# power_supply.net
KiCad netlist of a schematic drawn in Altium Designer
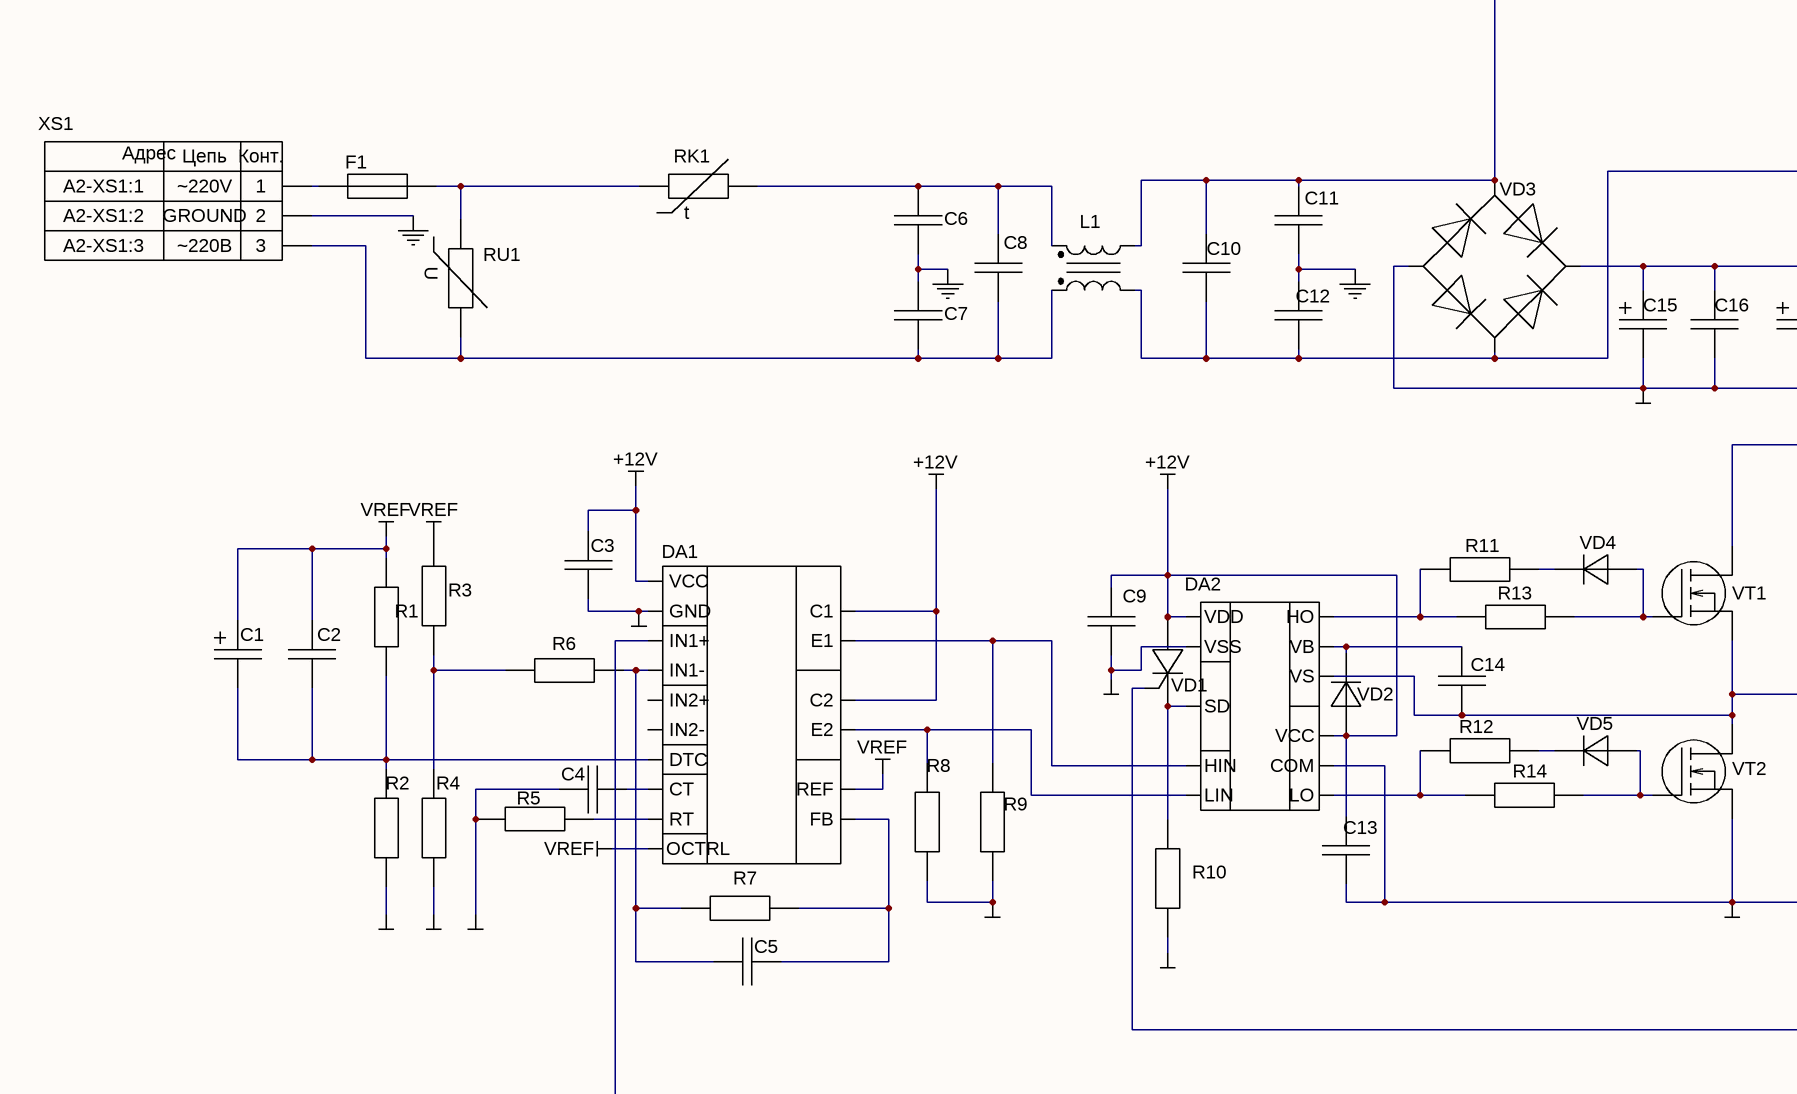
[diagram p0: power_supply.SchDoc, left]
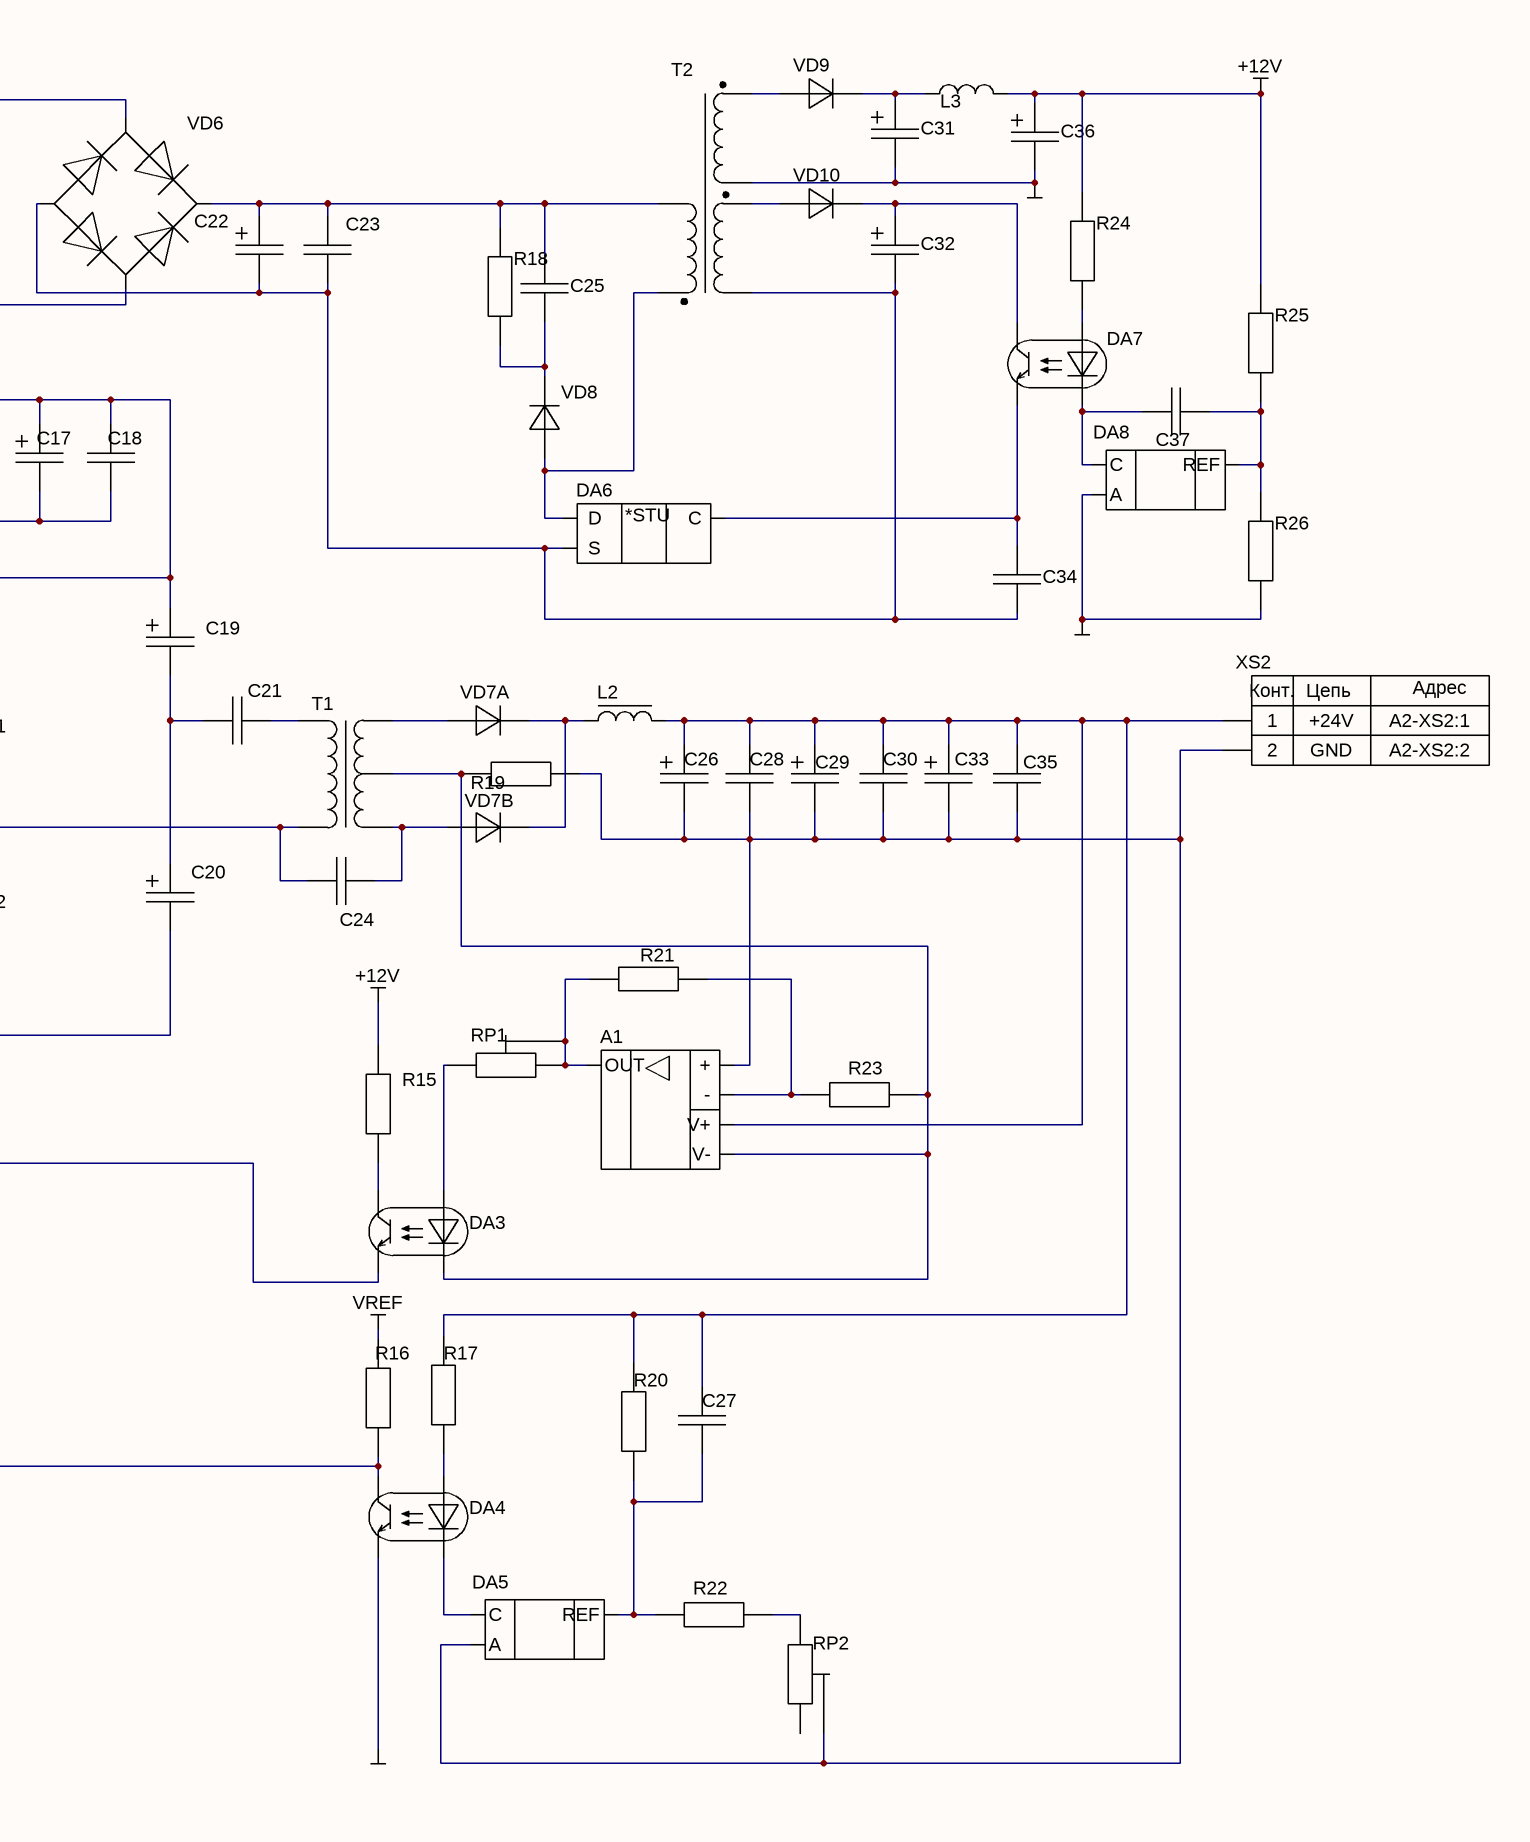
[diagram p1: power_supply.SchDoc, right]

(export (version "E")
  (design (tool "Eeschema 10.0.6"))
  (components
    (comp (ref "A1") (value "LMV321ILT") (libsource (lib "elems") (part "single_channel_op_amp")))
    (comp (ref "C1") (value "100мкФ") (libsource (lib "elems") (part "C_pol")))
    (comp (ref "C2") (value "100 нФ") (libsource (lib "elems") (part "C_const")))
    (comp (ref "C3") (value "1 мкФ") (libsource (lib "") (part "C_const_1")))
    (comp (ref "C4") (value "2.2 нФ") (libsource (lib "elems") (part "C_const")))
    (comp (ref "C5") (value "1 мкФ") (libsource (lib "elems") (part "C_const")))
    (comp (ref "C6") (value "1 нФ") (footprint "CAP: B32021") (libsource (lib "elems") (part "C_const")))
    (comp (ref "C7") (value "1 нФ") (footprint "CAP: B32021") (libsource (lib "elems") (part "C_const")))
    (comp (ref "C8") (value "470 нФ") (footprint "B32922") (libsource (lib "elems") (part "C_const")))
    (comp (ref "C9") (value "1 мкФ") (libsource (lib "elems") (part "C_const")))
    (comp (ref "C10") (value "470 нФ") (footprint "B32922") (libsource (lib "elems") (part "C_const")))
    (comp (ref "C11") (value "1 нФ") (footprint "CAP: B32021") (libsource (lib "elems") (part "C_const")))
    (comp (ref "C12") (value "1 нФ") (footprint "CAP: B32021") (libsource (lib "elems") (part "C_const")))
    (comp (ref "C13") (value "1 мкФ") (libsource (lib "elems") (part "C_const")))
    (comp (ref "C14") (value "1 мкФ") (libsource (lib "elems") (part "C_const")))
    (comp (ref "C15") (value "220 мкФ") (libsource (lib "elems") (part "C_pol")))
    (comp (ref "C16") (value "100 нФ") (libsource (lib "elems") (part "C_const")))
    (comp (ref "C17") (value "220 мкФ") (libsource (lib "elems") (part "C_pol")))
    (comp (ref "C18") (value "100 нФ") (libsource (lib "elems") (part "C_const")))
    (comp (ref "C19") (value "10 мкФ") (libsource (lib "elems") (part "C_pol")))
    (comp (ref "C20") (value "10 мкФ") (libsource (lib "elems") (part "C_pol")))
    (comp (ref "C21") (value "1 мкФ") (libsource (lib "") (part "C_const_2")))
    (comp (ref "C22") (value "100 мкФ") (libsource (lib "elems") (part "C_pol")))
    (comp (ref "C23") (value "100 нФ") (libsource (lib "elems") (part "C_const")))
    (comp (ref "C24") (value "1 нФ") (libsource (lib "elems") (part "C_const")))
    (comp (ref "C25") (value "C_const") (libsource (lib "elems") (part "C_const")))
    (comp (ref "C26") (value "3300 мкФ") (libsource (lib "elems") (part "C_pol")))
    (comp (ref "C27") (value "1 мкФ") (libsource (lib "elems") (part "C_const")))
    (comp (ref "C28") (value "100 нФ") (libsource (lib "elems") (part "C_const")))
    (comp (ref "C29") (value "3300 мкФ") (libsource (lib "elems") (part "C_pol")))
    (comp (ref "C30") (value "100 нФ") (libsource (lib "elems") (part "C_const")))
    (comp (ref "C31") (value "C_pol") (libsource (lib "elems") (part "C_pol")))
    (comp (ref "C32") (value "C_pol") (libsource (lib "elems") (part "C_pol")))
    (comp (ref "C33") (value "3300 мкФ") (libsource (lib "elems") (part "C_pol")))
    (comp (ref "C34") (value "C_const") (libsource (lib "elems") (part "C_const")))
    (comp (ref "C35") (value "100 нФ") (libsource (lib "elems") (part "C_const")))
    (comp (ref "C36") (value "C_pol") (libsource (lib "elems") (part "C_pol")))
    (comp (ref "C37") (value "C_const") (libsource (lib "elems") (part "C_const")))
    (comp (ref "DA1") (value "tl494") (libsource (lib "elems") (part "tl494")))
    (comp (ref "DA2") (value "ir2110") (libsource (lib "elems") (part "ir2110")))
    (comp (ref "DA3") (value "LTV-814") (libsource (lib "elems") (part "opt")))
    (comp (ref "DA4") (value "LTV-814") (libsource (lib "elems") (part "opt")))
    (comp (ref "DA5") (value "tl431") (libsource (lib "elems") (part "tl431")))
    (comp (ref "DA6") (value "top227") (libsource (lib "elems") (part "top227")))
    (comp (ref "DA7") (value "opt") (libsource (lib "elems") (part "opt")))
    (comp (ref "DA8") (value "tl431") (libsource (lib "elems") (part "tl431")))
    (comp (ref "F1") (value "2А") (footprint "FUSE: 1812") (libsource (lib "elems") (part "fuse")))
    (comp (ref "L1") (value "4.7 мГн") (footprint "IND: B82721") (libsource (lib "elems") (part "L_sin")))
    (comp (ref "L2") (value "choke") (libsource (lib "elems") (part "choke")))
    (comp (ref "L3") (value "L") (libsource (lib "elems") (part "L")))
    (comp (ref "R1") (value "91 кОм") (libsource (lib "") (part "Res_1")))
    (comp (ref "R2") (value "10 кОм") (libsource (lib "elems") (part "Res")))
    (comp (ref "R3") (value "5.1 кОм") (libsource (lib "") (part "Res_3")))
    (comp (ref "R4") (value "5.1 кОм") (libsource (lib "elems") (part "Res")))
    (comp (ref "R5") (value "12 кОм") (libsource (lib "elems") (part "Res")))
    (comp (ref "R6") (value "510 Ом") (libsource (lib "elems") (part "Res")))
    (comp (ref "R7") (value "51 кОм") (libsource (lib "elems") (part "Res")))
    (comp (ref "R8") (value "1 кОм") (libsource (lib "elems") (part "Res")))
    (comp (ref "R9") (value "1 кОм") (libsource (lib "elems") (part "Res")))
    (comp (ref "R10") (value "1 кОм") (libsource (lib "elems") (part "Res")))
    (comp (ref "R11") (value "22 Ом") (libsource (lib "elems") (part "Res")))
    (comp (ref "R12") (value "22 Ом") (libsource (lib "elems") (part "Res")))
    (comp (ref "R13") (value "22 Ом") (libsource (lib "elems") (part "Res")))
    (comp (ref "R14") (value "22 Ом") (libsource (lib "elems") (part "Res")))
    (comp (ref "R15") (value "1 кОм") (libsource (lib "elems") (part "Res")))
    (comp (ref "R16") (value "10 кОм") (libsource (lib "elems") (part "Res")))
    (comp (ref "R17") (value "680 Ом") (libsource (lib "elems") (part "Res")))
    (comp (ref "R18") (value "Res") (libsource (lib "") (part "Res_2")))
    (comp (ref "R19") (value "1 мОм") (libsource (lib "elems") (part "Res")))
    (comp (ref "R20") (value "22 кОм") (libsource (lib "elems") (part "Res")))
    (comp (ref "R21") (value "100 кОм") (libsource (lib "elems") (part "Res")))
    (comp (ref "R22") (value "2 кОм") (libsource (lib "elems") (part "Res")))
    (comp (ref "R23") (value "1 кОм") (libsource (lib "elems") (part "Res")))
    (comp (ref "R24") (value "Res") (libsource (lib "") (part "Res_2")))
    (comp (ref "R25") (value "Res") (libsource (lib "") (part "Res_2")))
    (comp (ref "R26") (value "Res") (libsource (lib "") (part "Res_2")))
    (comp (ref "RK1")
      (value "JNR15S121L")
      (footprint "RES: B57237 (NTC)")
      (libsource (lib "elems") (part "RK"))
    )
    (comp (ref "RP1") (value "5 кОм") (libsource (lib "elems") (part "pot")))
    (comp (ref "RP2") (value "5 кОм") (libsource (lib "elems") (part "pot")))
    (comp (ref "RU1")
      (value "MOV-07D431K")
      (footprint "RES: MOV-07D431K")
      (libsource (lib "elems") (part "RU"))
    )
    (comp (ref "T1") (value "Trans_1_2") (libsource (lib "elems") (part "Trans_1_2")))
    (comp (ref "T2") (value "trans_1_2_isol") (libsource (lib "elems") (part "trans_1_2_isol")))
    (comp (ref "VD1") (value "BT149D") (libsource (lib "elems") (part "tiristor")))
    (comp (ref "VD2") (value "1n4004") (libsource (lib "elems") (part "VD")))
    (comp (ref "VD3") (value "GBU6K-BP") (footprint "DIODE: GBU") (libsource (lib "elems") (part "d_bridge")))
    (comp (ref "VD4") (value "VS-HFA04TB60-M3") (libsource (lib "elems") (part "VD")))
    (comp (ref "VD5") (value "VS-HFA04TB60-M3") (libsource (lib "elems") (part "VD")))
    (comp (ref "VD6") (value "GBU6K-BP") (footprint "DIODE: GBU") (libsource (lib "elems") (part "d_bridge")))
    (comp (ref "VD7") (value "STPS30H100CT") (libsource (lib "elems") (part "pair_diodes_cat")))
    (comp (ref "VD8") (value "VD") (libsource (lib "elems") (part "VD")))
    (comp (ref "VD9") (value "VD") (libsource (lib "elems") (part "VD")))
    (comp (ref "VD10") (value "VD") (libsource (lib "elems") (part "VD")))
    (comp (ref "VT1") (value "STP9NK50Z") (libsource (lib "elems") (part "mosfet")))
    (comp (ref "VT2") (value "STP9NK50Z") (libsource (lib "") (part "mosfet_1")))
    (comp (ref "XS1")
      (value "X3")
      (fields
        (field (name "CIRCUIT1") "~220V")
        (field (name "CIRCUIT2") "GROUND")
        (field (name "CIRCUIT3") "~220В")
        (field (name "=ADDRESS1") "A2-XS1:1")
        (field (name "=ADDRESS2") "A2-XS1:2")
        (field (name "=ADDRESS3") "A2-XS1:3")
      )
      (libsource (lib "elems") (part "X3"))
    )
    (comp (ref "XS2")
      (value "X2")
      (fields
        (field (name "CIRCUIT2") "GND")
        (field (name "CIRCUIT1") "+24V")
        (field (name "=ADDRESS2") "A2-XS2:2")
        (field (name "=ADDRESS1") "A2-XS2:1")
      )
      (libsource (lib "elems") (part "X2"))
    )
  )
  (nets
    (net (code "1") (name "+12V") (class "Default")
      (node (ref "C13") (pin "2") (pinfunction "2_2") (pintype "passive"))
      (node (ref "C3") (pin "1") (pinfunction "1_1") (pintype "passive"))
      (node (ref "C36") (pin "1") (pinfunction "1_1") (pintype "passive"))
      (node (ref "C9") (pin "2") (pinfunction "2_2") (pintype "passive"))
      (node (ref "DA1") (pin "11") (pinfunction "C2_11") (pintype "passive"))
      (node (ref "DA1") (pin "12") (pinfunction "VCC_12") (pintype "passive"))
      (node (ref "DA1") (pin "8") (pinfunction "C1_8") (pintype "passive"))
      (node (ref "DA2") (pin "11") (pinfunction "VDD_11") (pintype "passive"))
      (node (ref "DA2") (pin "3") (pinfunction "VCC_3") (pintype "passive"))
      (node (ref "L3") (pin "2") (pinfunction "2_2") (pintype "passive"))
      (node (ref "R15") (pin "6") (pinfunction "6_6") (pintype "passive"))
      (node (ref "R24") (pin "2") (pinfunction "6_2") (pintype "passive"))
      (node (ref "R25") (pin "2") (pinfunction "6_2") (pintype "passive"))
      (node (ref "VD1") (pin "2") (pinfunction "2_2") (pintype "passive"))
      (node (ref "VD2") (pin "1") (pinfunction "1_1") (pintype "passive"))
    )
    (net (code "2") (name "GND") (class "Default")
      (node (ref "C13") (pin "1") (pinfunction "1_1") (pintype "passive"))
      (node (ref "C15") (pin "2") (pinfunction "2_2") (pintype "passive"))
      (node (ref "C16") (pin "1") (pinfunction "1_1") (pintype "passive"))
      (node (ref "C17") (pin "2") (pinfunction "2_2") (pintype "passive"))
      (node (ref "C18") (pin "1") (pinfunction "1_1") (pintype "passive"))
      (node (ref "C20") (pin "2") (pinfunction "2_2") (pintype "passive"))
      (node (ref "C3") (pin "2") (pinfunction "2_2") (pintype "passive"))
      (node (ref "C31") (pin "2") (pinfunction "2_2") (pintype "passive"))
      (node (ref "C36") (pin "2") (pinfunction "2_2") (pintype "passive"))
      (node (ref "C4") (pin "1") (pinfunction "1_1") (pintype "passive"))
      (node (ref "C9") (pin "1") (pinfunction "1_1") (pintype "passive"))
      (node (ref "DA1") (pin "7") (pinfunction "GND_7") (pintype "passive"))
      (node (ref "DA2") (pin "15") (pinfunction "VSS_15") (pintype "passive"))
      (node (ref "DA2") (pin "2") (pinfunction "COM_2") (pintype "passive"))
      (node (ref "DA4") (pin "4") (pinfunction "4_4") (pintype "passive"))
      (node (ref "DA8") (pin "3") (pinfunction "A_3") (pintype "passive"))
      (node (ref "R10") (pin "5") (pinfunction "59_5") (pintype "passive"))
      (node (ref "R2") (pin "5") (pinfunction "59_5") (pintype "passive"))
      (node (ref "R26") (pin "1") (pinfunction "1_1") (pintype "passive"))
      (node (ref "R4") (pin "5") (pinfunction "59_5") (pintype "passive"))
      (node (ref "R5") (pin "5") (pinfunction "59_5") (pintype "passive"))
      (node (ref "R8") (pin "5") (pinfunction "59_5") (pintype "passive"))
      (node (ref "R9") (pin "5") (pinfunction "59_5") (pintype "passive"))
      (node (ref "T2") (pin "4") (pinfunction "4_4") (pintype "passive"))
      (node (ref "VD3") (pin "4") (pinfunction "4_4") (pintype "passive"))
      (node (ref "VT2") (pin "25") (pinfunction "25_25") (pintype "passive"))
    )
    (net (code "3") (name "Net-(A1-+)") (class "Default")
      (node (ref "A1") (pin "1") (pinfunction "+_1") (pintype "passive"))
      (node (ref "C26") (pin "2") (pinfunction "2_2") (pintype "passive"))
      (node (ref "C28") (pin "1") (pinfunction "1_1") (pintype "passive"))
      (node (ref "C29") (pin "2") (pinfunction "2_2") (pintype "passive"))
      (node (ref "C30") (pin "2") (pinfunction "2_2") (pintype "passive"))
      (node (ref "C33") (pin "2") (pinfunction "2_2") (pintype "passive"))
      (node (ref "C35") (pin "2") (pinfunction "2_2") (pintype "passive"))
      (node (ref "DA5") (pin "3") (pinfunction "A_3") (pintype "passive"))
      (node (ref "R19") (pin "6") (pinfunction "6_6") (pintype "passive"))
      (node (ref "RP2") (pin "3") (pinfunction "3_3") (pintype "passive"))
      (node (ref "XS2") (pin "2") (pinfunction "2_2") (pintype "passive"))
    )
    (net (code "4") (name "Net-(A1--)") (class "Default")
      (node (ref "A1") (pin "3") (pinfunction "-_3") (pintype "passive"))
      (node (ref "R21") (pin "6") (pinfunction "6_6") (pintype "passive"))
      (node (ref "R23") (pin "5") (pinfunction "59_5") (pintype "passive"))
    )
    (net (code "5") (name "Net-(A1-OUT)") (class "Default")
      (node (ref "A1") (pin "4") (pinfunction "OUT_4") (pintype "passive"))
      (node (ref "R21") (pin "5") (pinfunction "59_5") (pintype "passive"))
      (node (ref "RP1") (pin "2") (pinfunction "2_2") (pintype "passive"))
      (node (ref "RP1") (pin "3") (pinfunction "3_3") (pintype "passive"))
    )
    (net (code "6") (name "Net-(A1-V+)") (class "Default")
      (node (ref "A1") (pin "5") (pinfunction "V+_5") (pintype "passive"))
      (node (ref "C26") (pin "1") (pinfunction "1_1") (pintype "passive"))
      (node (ref "C27") (pin "1") (pinfunction "1_1") (pintype "passive"))
      (node (ref "C28") (pin "2") (pinfunction "2_2") (pintype "passive"))
      (node (ref "C29") (pin "1") (pinfunction "1_1") (pintype "passive"))
      (node (ref "C30") (pin "1") (pinfunction "1_1") (pintype "passive"))
      (node (ref "C33") (pin "1") (pinfunction "1_1") (pintype "passive"))
      (node (ref "C35") (pin "1") (pinfunction "1_1") (pintype "passive"))
      (node (ref "L2") (pin "2") (pinfunction "2_2") (pintype "passive"))
      (node (ref "R17") (pin "5") (pinfunction "59_5") (pintype "passive"))
      (node (ref "R20") (pin "5") (pinfunction "59_5") (pintype "passive"))
      (node (ref "XS2") (pin "1") (pinfunction "1_1") (pintype "passive"))
    )
    (net (code "7") (name "Net-(A1-V-)") (class "Default")
      (node (ref "A1") (pin "2") (pinfunction "V-_2") (pintype "passive"))
      (node (ref "DA3") (pin "2") (pinfunction "2_2") (pintype "passive"))
      (node (ref "R19") (pin "5") (pinfunction "59_5") (pintype "passive"))
      (node (ref "R23") (pin "6") (pinfunction "6_6") (pintype "passive"))
      (node (ref "T1") (pin "5") (pinfunction "5_5") (pintype "passive"))
    )
    (net (code "8") (name "Net-(C6-Pad2)") (class "Default")
      (node (ref "C6") (pin "2") (pinfunction "2_2") (pintype "passive"))
      (node (ref "C8") (pin "2") (pinfunction "2_2") (pintype "passive"))
      (node (ref "L1") (pin "1") (pinfunction "1_1") (pintype "passive"))
      (node (ref "RK1") (pin "2") (pinfunction "2_2") (pintype "passive"))
    )
    (net (code "9") (name "Net-(C7-Pad1)") (class "Default")
      (node (ref "C7") (pin "1") (pinfunction "1_1") (pintype "passive"))
      (node (ref "C8") (pin "1") (pinfunction "1_1") (pintype "passive"))
      (node (ref "L1") (pin "3") (pinfunction "3_3") (pintype "passive"))
      (node (ref "RU1") (pin "2") (pinfunction "2_2") (pintype "passive"))
      (node (ref "XS1") (pin "3") (pinfunction "3_3") (pintype "passive"))
    )
    (net (code "10") (name "Net-(C10-Pad1)") (class "Default")
      (node (ref "C10") (pin "1") (pinfunction "1_1") (pintype "passive"))
      (node (ref "C12") (pin "2") (pinfunction "2_2") (pintype "passive"))
      (node (ref "L1") (pin "4") (pinfunction "4_4") (pintype "passive"))
      (node (ref "VD3") (pin "2") (pinfunction "2_2") (pintype "passive"))
      (node (ref "VD6") (pin "2") (pinfunction "2_2") (pintype "passive"))
    )
    (net (code "11") (name "Net-(C10-Pad2)") (class "Default")
      (node (ref "C10") (pin "2") (pinfunction "2_2") (pintype "passive"))
      (node (ref "C11") (pin "1") (pinfunction "1_1") (pintype "passive"))
      (node (ref "L1") (pin "2") (pinfunction "2_2") (pintype "passive"))
      (node (ref "VD3") (pin "1") (pinfunction "1_1") (pintype "passive"))
      (node (ref "VD6") (pin "1") (pinfunction "1_1") (pintype "passive"))
    )
    (net (code "12") (name "Net-(C15-Pad1)") (class "Default")
      (node (ref "C15") (pin "1") (pinfunction "1_1") (pintype "passive"))
      (node (ref "C16") (pin "2") (pinfunction "2_2") (pintype "passive"))
      (node (ref "C17") (pin "1") (pinfunction "1_1") (pintype "passive"))
      (node (ref "C18") (pin "2") (pinfunction "2_2") (pintype "passive"))
      (node (ref "C19") (pin "1") (pinfunction "1_1") (pintype "passive"))
      (node (ref "VD3") (pin "3") (pinfunction "3_3") (pintype "passive"))
      (node (ref "VT1") (pin "24") (pinfunction "24_24") (pintype "passive"))
    )
    (net (code "13") (name "Net-(C19-Pad2)") (class "Default")
      (node (ref "C19") (pin "2") (pinfunction "2_2") (pintype "passive"))
      (node (ref "C20") (pin "1") (pinfunction "1_1") (pintype "passive"))
      (node (ref "C21") (pin "1") (pinfunction "1_1") (pintype "passive"))
    )
    (net (code "14") (name "Net-(C21-Pad2)") (class "Default")
      (node (ref "C21") (pin "2") (pinfunction "2_2") (pintype "passive"))
      (node (ref "T1") (pin "1") (pinfunction "1_1") (pintype "passive"))
    )
    (net (code "15") (name "Net-(C25-Pad1)") (class "Default")
      (node (ref "C25") (pin "1") (pinfunction "1_1") (pintype "passive"))
      (node (ref "R18") (pin "1") (pinfunction "1_1") (pintype "passive"))
      (node (ref "VD8") (pin "2") (pinfunction "2_2") (pintype "passive"))
    )
    (net (code "16") (name "Net-(C31-Pad1)") (class "Default")
      (node (ref "C31") (pin "1") (pinfunction "1_1") (pintype "passive"))
      (node (ref "L3") (pin "1") (pinfunction "1_1") (pintype "passive"))
      (node (ref "VD9") (pin "2") (pinfunction "2_2") (pintype "passive"))
    )
    (net (code "17") (name "Net-(C32-Pad1)") (class "Default")
      (node (ref "C32") (pin "1") (pinfunction "1_1") (pintype "passive"))
      (node (ref "DA7") (pin "3") (pinfunction "3_3") (pintype "passive"))
      (node (ref "VD10") (pin "2") (pinfunction "2_2") (pintype "passive"))
    )
    (net (code "18") (name "Net-(DA1-CT)") (class "Default")
      (node (ref "C4") (pin "2") (pinfunction "2_2") (pintype "passive"))
      (node (ref "DA1") (pin "5") (pinfunction "CT_5") (pintype "passive"))
    )
    (net (code "19") (name "Net-(DA1-DTC)") (class "Default")
      (node (ref "C1") (pin "2") (pinfunction "2_2") (pintype "passive"))
      (node (ref "C2") (pin "1") (pinfunction "1_1") (pintype "passive"))
      (node (ref "DA1") (pin "4") (pinfunction "DTC_4") (pintype "passive"))
      (node (ref "R1") (pin "6") (pinfunction "6_6") (pintype "passive"))
      (node (ref "R2") (pin "6") (pinfunction "6_6") (pintype "passive"))
    )
    (net (code "20") (name "Net-(DA1-E1)") (class "Default")
      (node (ref "DA1") (pin "9") (pinfunction "E1_9") (pintype "passive"))
      (node (ref "DA2") (pin "12") (pinfunction "HIN_12") (pintype "passive"))
      (node (ref "R9") (pin "6") (pinfunction "6_6") (pintype "passive"))
    )
    (net (code "21") (name "Net-(DA1-E2)") (class "Default")
      (node (ref "DA1") (pin "10") (pinfunction "E2_10") (pintype "passive"))
      (node (ref "DA2") (pin "14") (pinfunction "LIN_14") (pintype "passive"))
      (node (ref "R8") (pin "6") (pinfunction "6_6") (pintype "passive"))
    )
    (net (code "22") (name "Net-(DA1-FB)") (class "Default")
      (node (ref "C5") (pin "2") (pinfunction "2_2") (pintype "passive"))
      (node (ref "DA1") (pin "3") (pinfunction "FB_3") (pintype "passive"))
      (node (ref "R7") (pin "6") (pinfunction "6_6") (pintype "passive"))
    )
    (net (code "23") (name "Net-(DA1-IN1+)") (class "Default")
      (node (ref "DA1") (pin "1") (pinfunction "IN1+_1") (pintype "passive"))
      (node (ref "DA4") (pin "3") (pinfunction "3_3") (pintype "passive"))
      (node (ref "R16") (pin "6") (pinfunction "6_6") (pintype "passive"))
    )
    (net (code "24") (name "Net-(DA1-IN1-)") (class "Default")
      (node (ref "C5") (pin "1") (pinfunction "1_1") (pintype "passive"))
      (node (ref "DA1") (pin "2") (pinfunction "IN1-_2") (pintype "passive"))
      (node (ref "R6") (pin "6") (pinfunction "6_6") (pintype "passive"))
      (node (ref "R7") (pin "5") (pinfunction "59_5") (pintype "passive"))
    )
    (net (code "25") (name "Net-(DA1-RT)") (class "Default")
      (node (ref "DA1") (pin "6") (pinfunction "RT_6") (pintype "passive"))
      (node (ref "R5") (pin "6") (pinfunction "6_6") (pintype "passive"))
    )
    (net (code "26") (name "Net-(DA2-HO)") (class "Default")
      (node (ref "DA2") (pin "8") (pinfunction "HO_8") (pintype "passive"))
      (node (ref "R11") (pin "5") (pinfunction "59_5") (pintype "passive"))
      (node (ref "R13") (pin "5") (pinfunction "59_5") (pintype "passive"))
    )
    (net (code "27") (name "Net-(DA2-LO)") (class "Default")
      (node (ref "DA2") (pin "1") (pinfunction "LO_1") (pintype "passive"))
      (node (ref "R12") (pin "5") (pinfunction "59_5") (pintype "passive"))
      (node (ref "R14") (pin "5") (pinfunction "59_5") (pintype "passive"))
    )
    (net (code "28") (name "Net-(DA2-SD)") (class "Default")
      (node (ref "DA2") (pin "13") (pinfunction "SD_13") (pintype "passive"))
      (node (ref "R10") (pin "6") (pinfunction "6_6") (pintype "passive"))
      (node (ref "VD1") (pin "1") (pinfunction "1_1") (pintype "passive"))
    )
    (net (code "29") (name "Net-(DA2-VB)") (class "Default")
      (node (ref "C14") (pin "1") (pinfunction "1_1") (pintype "passive"))
      (node (ref "DA2") (pin "7") (pinfunction "VB_7") (pintype "passive"))
      (node (ref "VD2") (pin "2") (pinfunction "2_2") (pintype "passive"))
    )
    (net (code "30") (name "Net-(DA2-VS)") (class "Default")
      (node (ref "C14") (pin "2") (pinfunction "2_2") (pintype "passive"))
      (node (ref "C24") (pin "1") (pinfunction "1_1") (pintype "passive"))
      (node (ref "DA2") (pin "6") (pinfunction "VS_6") (pintype "passive"))
      (node (ref "T1") (pin "2") (pinfunction "2_2") (pintype "passive"))
      (node (ref "VT1") (pin "25") (pinfunction "25_25") (pintype "passive"))
      (node (ref "VT2") (pin "24") (pinfunction "24_24") (pintype "passive"))
    )
    (net (code "31") (name "Net-(DA3-Pad1)") (class "Default")
      (node (ref "DA3") (pin "1") (pinfunction "1_1") (pintype "passive"))
      (node (ref "RP1") (pin "1") (pinfunction "1_1") (pintype "passive"))
    )
    (net (code "32") (name "Net-(DA3-Pad4)") (class "Default")
      (node (ref "DA3") (pin "4") (pinfunction "4_4") (pintype "passive"))
      (node (ref "VD1") (pin "3") (pinfunction "3_3") (pintype "passive"))
    )
    (net (code "33") (name "Net-(DA4-Pad1)") (class "Default")
      (node (ref "DA4") (pin "1") (pinfunction "1_1") (pintype "passive"))
      (node (ref "R17") (pin "6") (pinfunction "6_6") (pintype "passive"))
    )
    (net (code "34") (name "Net-(DA5-C)") (class "Default")
      (node (ref "DA4") (pin "2") (pinfunction "2_2") (pintype "passive"))
      (node (ref "DA5") (pin "1") (pinfunction "C_1") (pintype "passive"))
    )
    (net (code "35") (name "Net-(DA5-REF)") (class "Default")
      (node (ref "C27") (pin "2") (pinfunction "2_2") (pintype "passive"))
      (node (ref "DA5") (pin "2") (pinfunction "REF_2") (pintype "passive"))
      (node (ref "R20") (pin "6") (pinfunction "6_6") (pintype "passive"))
      (node (ref "R22") (pin "5") (pinfunction "59_5") (pintype "passive"))
    )
    (net (code "36") (name "Net-(DA6-C)") (class "Default")
      (node (ref "C34") (pin "2") (pinfunction "2_2") (pintype "passive"))
      (node (ref "DA6") (pin "3") (pinfunction "C_3") (pintype "passive"))
      (node (ref "DA7") (pin "4") (pinfunction "4_4") (pintype "passive"))
    )
    (net (code "37") (name "Net-(DA6-D)") (class "Default")
      (node (ref "DA6") (pin "1") (pinfunction "D_1") (pintype "passive"))
      (node (ref "T2") (pin "2") (pinfunction "2_2") (pintype "passive"))
      (node (ref "VD8") (pin "1") (pinfunction "1_1") (pintype "passive"))
    )
    (net (code "38") (name "Net-(DA6-S)") (class "Default")
      (node (ref "C22") (pin "2") (pinfunction "2_2") (pintype "passive"))
      (node (ref "C23") (pin "2") (pinfunction "2_2") (pintype "passive"))
      (node (ref "C32") (pin "2") (pinfunction "2_2") (pintype "passive"))
      (node (ref "C34") (pin "1") (pinfunction "1_1") (pintype "passive"))
      (node (ref "DA6") (pin "2") (pinfunction "S_2") (pintype "passive"))
      (node (ref "T2") (pin "4") (pinfunction "4_4") (pintype "passive"))
      (node (ref "VD6") (pin "4") (pinfunction "4_4") (pintype "passive"))
    )
    (net (code "39") (name "Net-(DA7-Pad1)") (class "Default")
      (node (ref "DA7") (pin "1") (pinfunction "1_1") (pintype "passive"))
      (node (ref "R24") (pin "1") (pinfunction "1_1") (pintype "passive"))
    )
    (net (code "40") (name "Net-(DA8-C)") (class "Default")
      (node (ref "C37") (pin "2") (pinfunction "2_2") (pintype "passive"))
      (node (ref "DA7") (pin "2") (pinfunction "2_2") (pintype "passive"))
      (node (ref "DA8") (pin "1") (pinfunction "C_1") (pintype "passive"))
    )
    (net (code "41") (name "Net-(DA8-REF)") (class "Default")
      (node (ref "C37") (pin "1") (pinfunction "1_1") (pintype "passive"))
      (node (ref "DA8") (pin "2") (pinfunction "REF_2") (pintype "passive"))
      (node (ref "R25") (pin "1") (pinfunction "1_1") (pintype "passive"))
      (node (ref "R26") (pin "2") (pinfunction "6_2") (pintype "passive"))
    )
    (net (code "42") (name "Net-(F1-Pad1)") (class "Default")
      (node (ref "F1") (pin "1") (pinfunction "1_1") (pintype "passive"))
      (node (ref "XS1") (pin "1") (pinfunction "1_1") (pintype "passive"))
    )
    (net (code "43") (name "Net-(F1-Pad2)") (class "Default")
      (node (ref "F1") (pin "2") (pinfunction "2_2") (pintype "passive"))
      (node (ref "RK1") (pin "1") (pinfunction "1_1") (pintype "passive"))
      (node (ref "RU1") (pin "1") (pinfunction "1_1") (pintype "passive"))
    )
    (net (code "44") (name "Net-(R3-59)") (class "Default")
      (node (ref "R3") (pin "5") (pinfunction "59_5") (pintype "passive"))
      (node (ref "R4") (pin "6") (pinfunction "6_6") (pintype "passive"))
      (node (ref "R6") (pin "5") (pinfunction "59_5") (pintype "passive"))
    )
    (net (code "45") (name "Net-(R11-Pad6)") (class "Default")
      (node (ref "R11") (pin "6") (pinfunction "6_6") (pintype "passive"))
      (node (ref "VD4") (pin "2") (pinfunction "2_2") (pintype "passive"))
    )
    (net (code "46") (name "Net-(R12-Pad6)") (class "Default")
      (node (ref "R12") (pin "6") (pinfunction "6_6") (pintype "passive"))
      (node (ref "VD5") (pin "2") (pinfunction "2_2") (pintype "passive"))
    )
    (net (code "47") (name "Net-(R13-Pad6)") (class "Default")
      (node (ref "R13") (pin "6") (pinfunction "6_6") (pintype "passive"))
      (node (ref "VD4") (pin "1") (pinfunction "1_1") (pintype "passive"))
      (node (ref "VT1") (pin "26") (pinfunction "26_26") (pintype "passive"))
    )
    (net (code "48") (name "Net-(R14-Pad6)") (class "Default")
      (node (ref "R14") (pin "6") (pinfunction "6_6") (pintype "passive"))
      (node (ref "VD5") (pin "1") (pinfunction "1_1") (pintype "passive"))
      (node (ref "VT2") (pin "26") (pinfunction "26_26") (pintype "passive"))
    )
    (net (code "49") (name "Net-(R15-59)") (class "Default")
      (node (ref "DA3") (pin "3") (pinfunction "3_3") (pintype "passive"))
      (node (ref "R15") (pin "5") (pinfunction "59_5") (pintype "passive"))
    )
    (net (code "50") (name "Net-(R18-6)") (class "Default")
      (node (ref "C22") (pin "1") (pinfunction "1_1") (pintype "passive"))
      (node (ref "C23") (pin "1") (pinfunction "1_1") (pintype "passive"))
      (node (ref "C25") (pin "2") (pinfunction "2_2") (pintype "passive"))
      (node (ref "R18") (pin "2") (pinfunction "6_2") (pintype "passive"))
      (node (ref "T2") (pin "1") (pinfunction "1_1") (pintype "passive"))
      (node (ref "VD6") (pin "3") (pinfunction "3_3") (pintype "passive"))
    )
    (net (code "51") (name "Net-(R22-Pad6)") (class "Default")
      (node (ref "R22") (pin "6") (pinfunction "6_6") (pintype "passive"))
      (node (ref "RP2") (pin "1") (pinfunction "1_1") (pintype "passive"))
    )
    (net (code "52") (name "Net-(T2-Pad3)") (class "Default")
      (node (ref "T2") (pin "3") (pinfunction "3_3") (pintype "passive"))
      (node (ref "VD9") (pin "1") (pinfunction "1_1") (pintype "passive"))
    )
    (net (code "53") (name "Net-(T2-Pad3)_1") (class "Default")
      (node (ref "T2") (pin "3") (pinfunction "3_3") (pintype "passive"))
      (node (ref "VD10") (pin "1") (pinfunction "1_1") (pintype "passive"))
    )
    (net (code "54") (name "Net-(VD7A-A1)") (class "Default")
      (node (ref "T1") (pin "3") (pinfunction "3_3") (pintype "passive"))
      (node (ref "VD7") (pin "1") (pinfunction "A1_1") (pintype "passive"))
    )
    (net (code "55") (name "Net-(VD7A-K)") (class "Default")
      (node (ref "L2") (pin "1") (pinfunction "1_1") (pintype "passive"))
      (node (ref "VD7") (pin "2") (pinfunction "K_2") (pintype "passive"))
    )
    (net (code "56") (name "Net-(VD7B-A2)") (class "Default")
      (node (ref "C24") (pin "2") (pinfunction "2_2") (pintype "passive"))
      (node (ref "T1") (pin "4") (pinfunction "4_4") (pintype "passive"))
      (node (ref "VD7") (pin "3") (pinfunction "A2_3") (pintype "passive"))
    )
    (net (code "57") (name "SH") (class "Default")
      (node (ref "C11") (pin "2") (pinfunction "2_2") (pintype "passive"))
      (node (ref "C12") (pin "1") (pinfunction "1_1") (pintype "passive"))
      (node (ref "C6") (pin "1") (pinfunction "1_1") (pintype "passive"))
      (node (ref "C7") (pin "2") (pinfunction "2_2") (pintype "passive"))
      (node (ref "XS1") (pin "2") (pinfunction "2_2") (pintype "passive"))
    )
    (net (code "58") (name "VREF") (class "Default")
      (node (ref "C1") (pin "1") (pinfunction "1_1") (pintype "passive"))
      (node (ref "C2") (pin "2") (pinfunction "2_2") (pintype "passive"))
      (node (ref "DA1") (pin "13") (pinfunction "OCTRL_13") (pintype "passive"))
      (node (ref "DA1") (pin "14") (pinfunction "REF_14") (pintype "passive"))
      (node (ref "R1") (pin "5") (pinfunction "59_5") (pintype "passive"))
      (node (ref "R16") (pin "5") (pinfunction "59_5") (pintype "passive"))
      (node (ref "R3") (pin "6") (pinfunction "6_6") (pintype "passive"))
    )
    (net (code "59") (name "unconnected-(DA1-IN2+-Pad16)") (class "Default")
      (node (ref "DA1") (pin "16") (pinfunction "IN2+_16") (pintype "passive"))
    )
    (net (code "60") (name "unconnected-(DA1-IN2--Pad15)") (class "Default")
      (node (ref "DA1") (pin "15") (pinfunction "IN2-_15") (pintype "passive"))
    )
    (net (code "61") (name "unconnected-(RP2-Pad2)") (class "Default")
      (node (ref "RP2") (pin "2") (pinfunction "2_2") (pintype "passive"))
    )
  )
)
